# XKT3619_wireless_charging_driver_R.net
KiCad netlist of a schematic drawn in Altium Designer
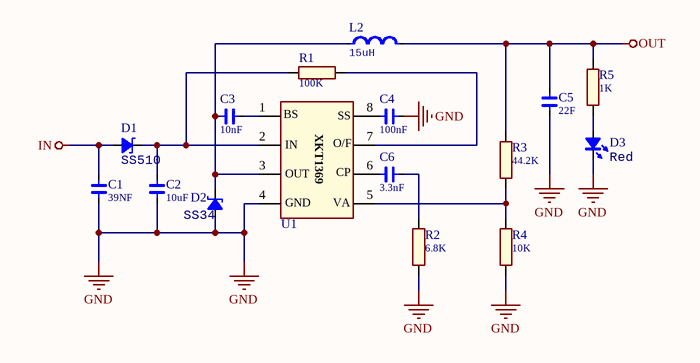
[diagram p0: XKT3619_wireless_charging_driver_R.SchDoc]

(export (version "E")
  (design (tool "Eeschema 10.0.6"))
  (components
    (comp (ref "C1")
      (value "39NF")
      (footprint "CAP_1206")
      (fields (field (name "Comment") "Cap"))
      (libsource (lib "") (part "Cap_1"))
    )
    (comp (ref "C2")
      (value "10uF")
      (footprint "CAP_1206")
      (fields (field (name "Comment") "Cap"))
      (libsource (lib "") (part "Cap_1"))
    )
    (comp (ref "C3")
      (value "10nF")
      (footprint "CAP_0603")
      (fields (field (name "Comment") "Cap"))
      (libsource (lib "Passive") (part "Cap"))
    )
    (comp (ref "C4")
      (value "100nF")
      (footprint "CAP_0603")
      (fields (field (name "Comment") "Cap"))
      (libsource (lib "Passive") (part "Cap"))
    )
    (comp (ref "C5")
      (value "22F")
      (footprint "CAP_1206")
      (fields (field (name "Comment") "Cap"))
      (libsource (lib "") (part "Cap_1"))
    )
    (comp (ref "C6")
      (value "3.3nF")
      (footprint "CAP_0603")
      (fields (field (name "Comment") "Cap"))
      (libsource (lib "Passive") (part "Cap"))
    )
    (comp (ref "D1")
      (value "SS510")
      (footprint "DO-214AB")
      (description "Schottky Diode")
      (libsource (lib "Active") (part "SchottkyDiode"))
    )
    (comp (ref "D2")
      (value "SS34")
      (footprint "DO-214AC")
      (description "Schottky Diode")
      (libsource (lib "Active") (part "SchottkyDiode"))
    )
    (comp (ref "D3")
      (value "Red")
      (footprint "LED_0805")
      (description "LED")
      (libsource (lib "Active") (part "LED"))
    )
    (comp (ref "L2")
      (value "15uH")
      (footprint "IND_CD75")
      (description "Inductor")
      (fields (field (name "Comment") "Ind"))
      (libsource (lib "Passive") (part "Ind"))
    )
    (comp (ref "R1")
      (value "100K")
      (footprint "RES_0603")
      (fields (field (name "Comment") "Res"))
      (libsource (lib "Passive") (part "Res"))
    )
    (comp (ref "R2")
      (value "6.8K")
      (footprint "RES_0603")
      (fields (field (name "Comment") "Res"))
      (libsource (lib "") (part "Res_1"))
    )
    (comp (ref "R3")
      (value "44.2K")
      (footprint "RES_0603")
      (fields (field (name "Comment") "Res"))
      (libsource (lib "") (part "Res_1"))
    )
    (comp (ref "R4")
      (value "10K")
      (footprint "RES_0603")
      (fields (field (name "Comment") "Res"))
      (libsource (lib "") (part "Res_1"))
    )
    (comp (ref "R5")
      (value "1K")
      (footprint "RES_0805")
      (fields (field (name "Comment") "Res"))
      (libsource (lib "") (part "Res_1"))
    )
    (comp (ref "U1")
      (value "XLT-3169")
      (footprint "SOP8_M")
      (description "XKT-3169 是芯科泰无线充电系列通用接收集成电路，体积小输出功率大，可配合各种无线充电方案应用，电路简单使用方便")
      (libsource (lib "Misc") (part "XLT-3169"))
    )
  )
  (nets
    (net (code "1") (name "GND") (class "Default")
      (node (ref "C1") (pin "1") (pinfunction "1_1") (pintype "passive"))
      (node (ref "C2") (pin "1") (pinfunction "1_1") (pintype "passive"))
      (node (ref "C4") (pin "2") (pinfunction "2_2") (pintype "passive"))
      (node (ref "C5") (pin "1") (pinfunction "1_1") (pintype "passive"))
      (node (ref "D2") (pin "1") (pinfunction "A_1") (pintype "passive"))
      (node (ref "D3") (pin "2") (pinfunction "K_2") (pintype "passive"))
      (node (ref "R2") (pin "1") (pinfunction "1_1") (pintype "passive"))
      (node (ref "R4") (pin "1") (pinfunction "1_1") (pintype "passive"))
      (node (ref "U1") (pin "4") (pinfunction "GND_4") (pintype "passive"))
    )
    (net (code "2") (name "IN") (class "Default")
      (node (ref "C1") (pin "2") (pinfunction "2_2") (pintype "passive"))
      (node (ref "D1") (pin "1") (pinfunction "A_1") (pintype "passive"))
    )
    (net (code "3") (name "Net-(C6-Pad2)") (class "Default")
      (node (ref "C6") (pin "2") (pinfunction "2_2") (pintype "passive"))
      (node (ref "R2") (pin "2") (pinfunction "2_2") (pintype "passive"))
    )
    (net (code "4") (name "Net-(D1-K)") (class "Default")
      (node (ref "C2") (pin "2") (pinfunction "2_2") (pintype "passive"))
      (node (ref "D1") (pin "2") (pinfunction "K_2") (pintype "passive"))
      (node (ref "R1") (pin "1") (pinfunction "1_1") (pintype "passive"))
      (node (ref "U1") (pin "2") (pinfunction "IN_2") (pintype "passive"))
    )
    (net (code "5") (name "Net-(D2-K)") (class "Default")
      (node (ref "C3") (pin "1") (pinfunction "1_1") (pintype "passive"))
      (node (ref "D2") (pin "2") (pinfunction "K_2") (pintype "passive"))
      (node (ref "L2") (pin "1") (pinfunction "1_1") (pintype "passive"))
      (node (ref "U1") (pin "3") (pinfunction "OUT_3") (pintype "passive"))
    )
    (net (code "6") (name "Net-(D3-A)") (class "Default")
      (node (ref "D3") (pin "1") (pinfunction "A_1") (pintype "passive"))
      (node (ref "R5") (pin "1") (pinfunction "1_1") (pintype "passive"))
    )
    (net (code "7") (name "Net-(U1-BS)") (class "Default")
      (node (ref "C3") (pin "2") (pinfunction "2_2") (pintype "passive"))
      (node (ref "U1") (pin "1") (pinfunction "BS_1") (pintype "passive"))
    )
    (net (code "8") (name "Net-(U1-CP)") (class "Default")
      (node (ref "C6") (pin "1") (pinfunction "1_1") (pintype "passive"))
      (node (ref "U1") (pin "6") (pinfunction "CP_6") (pintype "passive"))
    )
    (net (code "9") (name "Net-(U1-O{slash}F)") (class "Default")
      (node (ref "R1") (pin "2") (pinfunction "2_2") (pintype "passive"))
      (node (ref "U1") (pin "7") (pinfunction "O/F_7") (pintype "passive"))
    )
    (net (code "10") (name "Net-(U1-SS)") (class "Default")
      (node (ref "C4") (pin "1") (pinfunction "1_1") (pintype "passive"))
      (node (ref "U1") (pin "8") (pinfunction "SS_8") (pintype "passive"))
    )
    (net (code "11") (name "Net-(U1-VA)") (class "Default")
      (node (ref "R3") (pin "1") (pinfunction "1_1") (pintype "passive"))
      (node (ref "R4") (pin "2") (pinfunction "2_2") (pintype "passive"))
      (node (ref "U1") (pin "5") (pinfunction "VA_5") (pintype "passive"))
    )
    (net (code "12") (name "OUT") (class "Default")
      (node (ref "C5") (pin "2") (pinfunction "2_2") (pintype "passive"))
      (node (ref "L2") (pin "2") (pinfunction "2_2") (pintype "passive"))
      (node (ref "R3") (pin "2") (pinfunction "2_2") (pintype "passive"))
      (node (ref "R5") (pin "2") (pinfunction "2_2") (pintype "passive"))
    )
  )
)
